# 2.net
KiCad netlist of a schematic drawn in Altium Designer
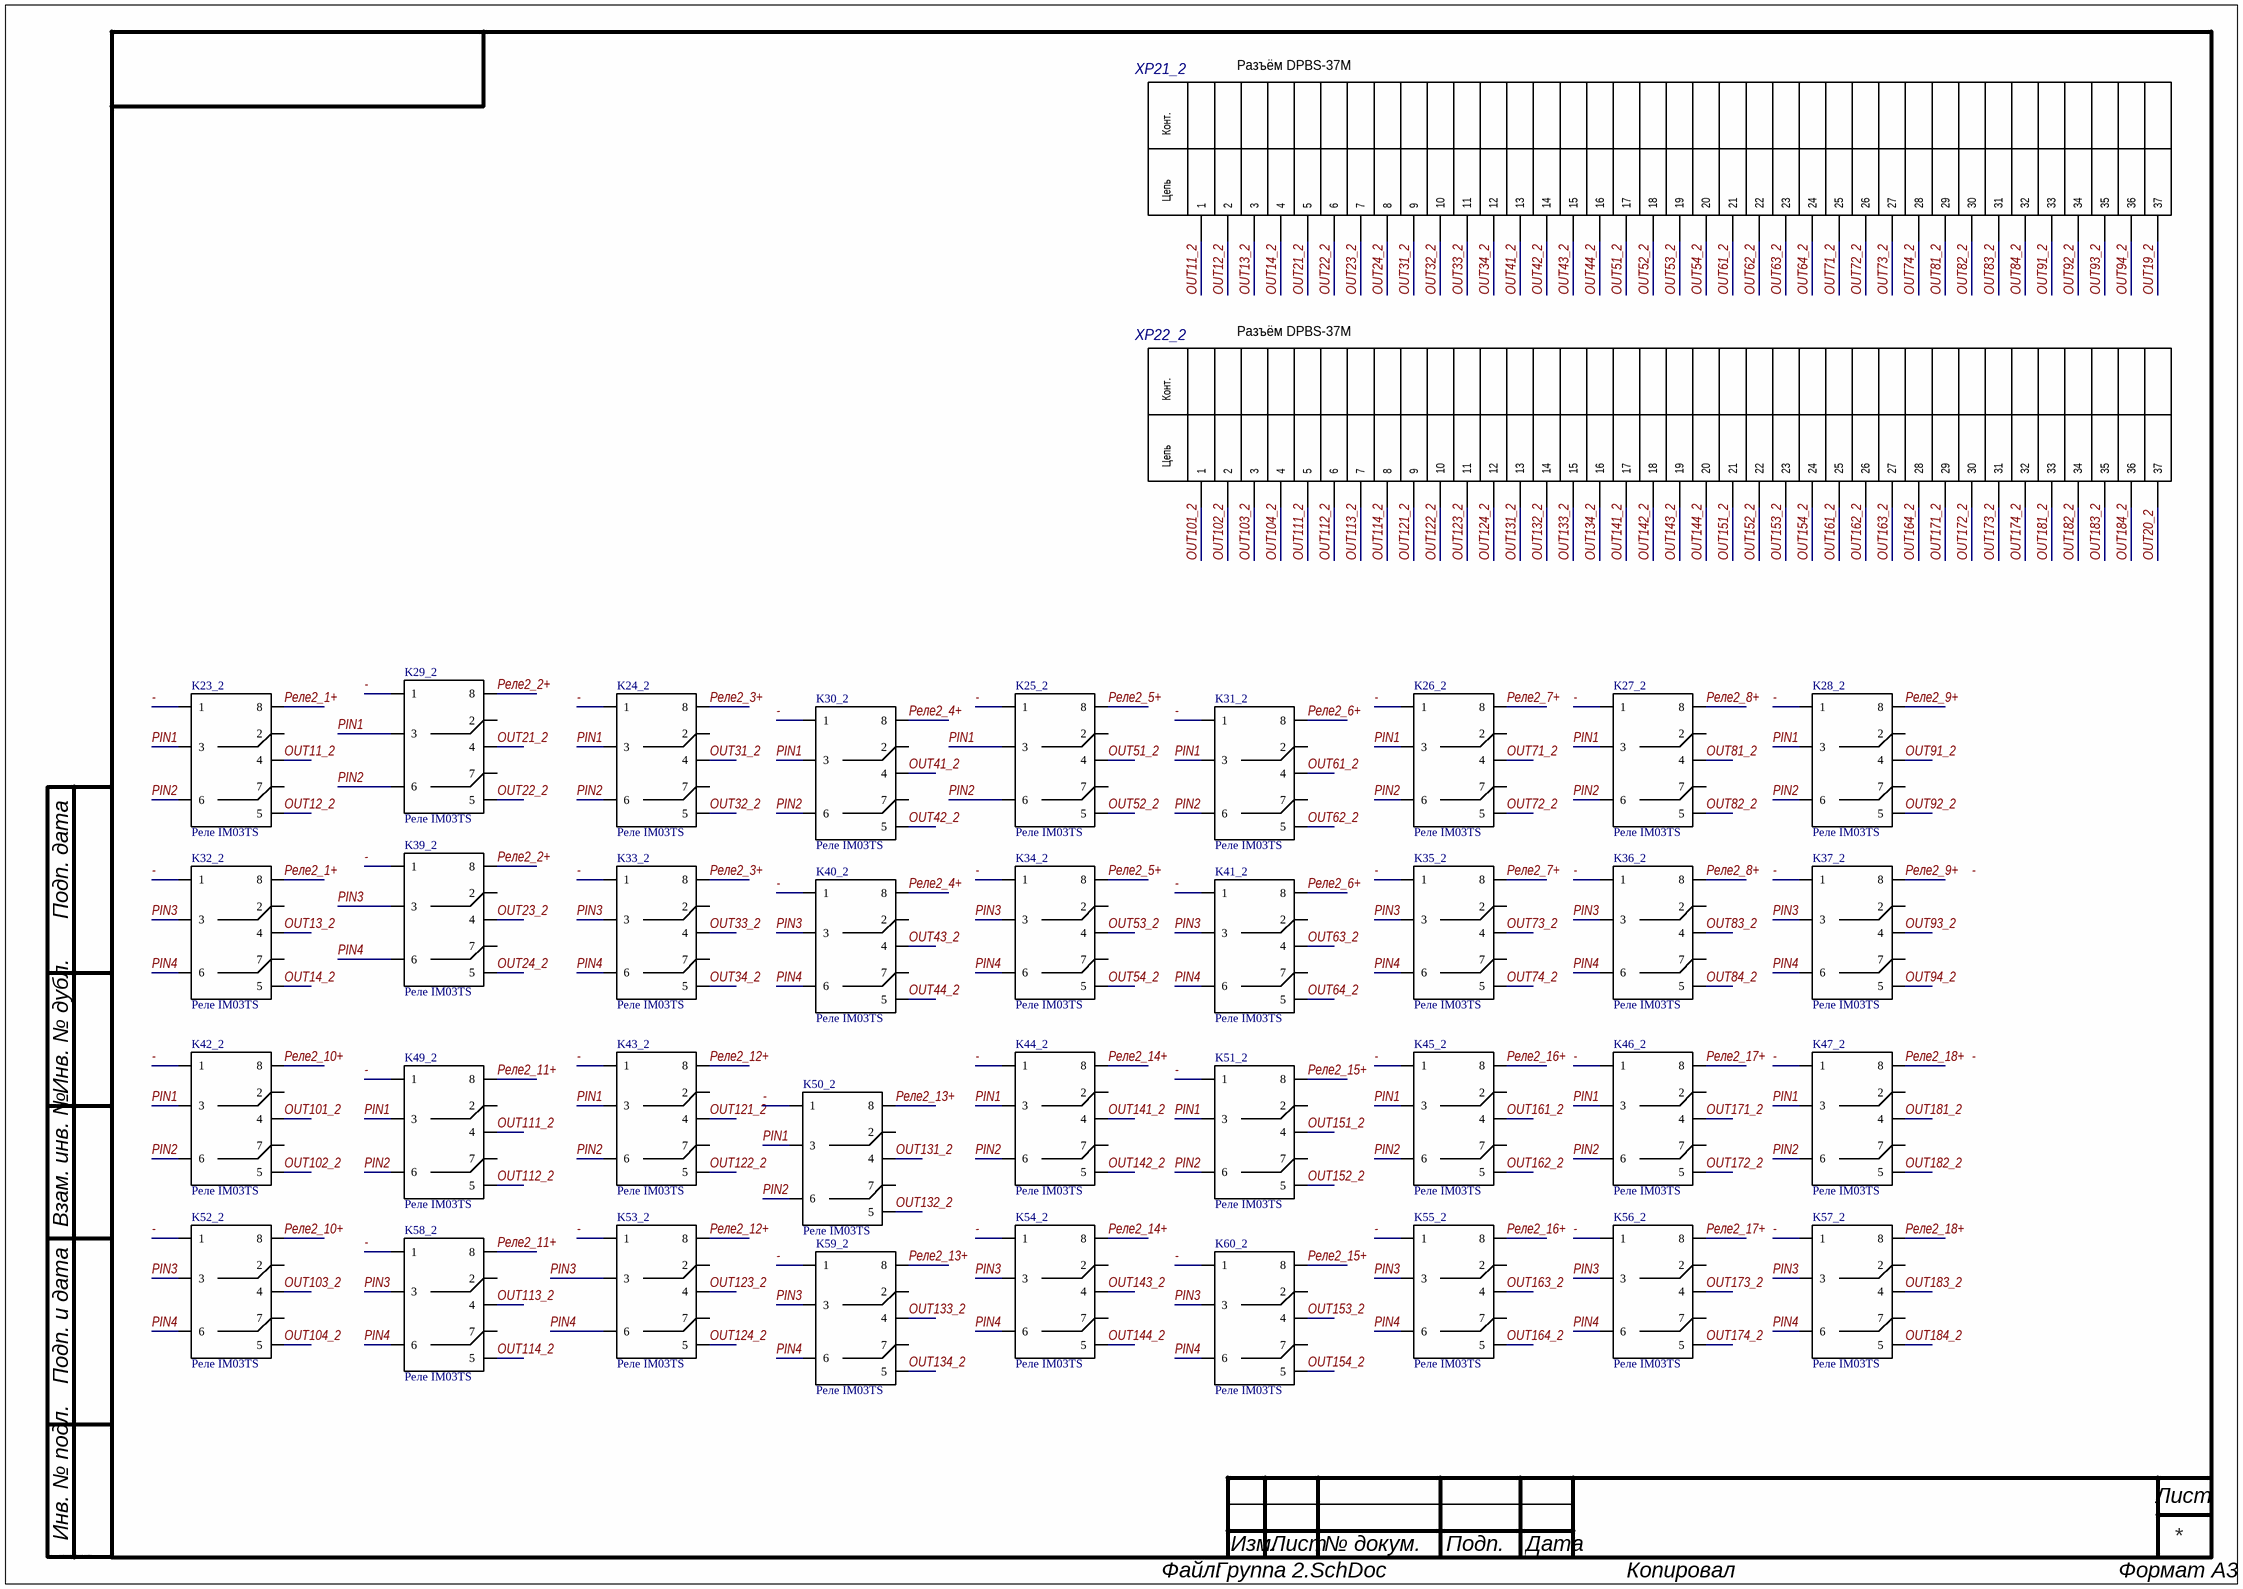
[diagram p0: Группа 2.SchDoc]

(export (version "E")
  (design (tool "Eeschema 10.0.6"))
  (components
    (comp (ref "K23_2")
      (value "Реле IM03TS")
      (footprint "IM03TS")
      (description "Реле")
      (libsource (lib "MainLibrary") (part "IM03TS"))
    )
    (comp (ref "K24_2")
      (value "Реле IM03TS")
      (footprint "IM03TS")
      (description "Реле")
      (libsource (lib "MainLibrary") (part "IM03TS"))
    )
    (comp (ref "K25_2")
      (value "Реле IM03TS")
      (footprint "IM03TS")
      (description "Реле")
      (libsource (lib "MainLibrary") (part "IM03TS"))
    )
    (comp (ref "K26_2")
      (value "Реле IM03TS")
      (footprint "IM03TS")
      (description "Реле")
      (libsource (lib "MainLibrary") (part "IM03TS"))
    )
    (comp (ref "K27_2")
      (value "Реле IM03TS")
      (footprint "IM03TS")
      (description "Реле")
      (libsource (lib "MainLibrary") (part "IM03TS"))
    )
    (comp (ref "K28_2")
      (value "Реле IM03TS")
      (footprint "IM03TS")
      (description "Реле")
      (libsource (lib "MainLibrary") (part "IM03TS"))
    )
    (comp (ref "K29_2")
      (value "Реле IM03TS")
      (footprint "IM03TS")
      (description "Реле")
      (libsource (lib "MainLibrary") (part "IM03TS"))
    )
    (comp (ref "K30_2")
      (value "Реле IM03TS")
      (footprint "IM03TS")
      (description "Реле")
      (libsource (lib "MainLibrary") (part "IM03TS"))
    )
    (comp (ref "K31_2")
      (value "Реле IM03TS")
      (footprint "IM03TS")
      (description "Реле")
      (libsource (lib "MainLibrary") (part "IM03TS"))
    )
    (comp (ref "K32_2")
      (value "Реле IM03TS")
      (footprint "IM03TS")
      (description "Реле")
      (libsource (lib "MainLibrary") (part "IM03TS"))
    )
    (comp (ref "K33_2")
      (value "Реле IM03TS")
      (footprint "IM03TS")
      (description "Реле")
      (libsource (lib "MainLibrary") (part "IM03TS"))
    )
    (comp (ref "K34_2")
      (value "Реле IM03TS")
      (footprint "IM03TS")
      (description "Реле")
      (libsource (lib "MainLibrary") (part "IM03TS"))
    )
    (comp (ref "K35_2")
      (value "Реле IM03TS")
      (footprint "IM03TS")
      (description "Реле")
      (libsource (lib "MainLibrary") (part "IM03TS"))
    )
    (comp (ref "K36_2")
      (value "Реле IM03TS")
      (footprint "IM03TS")
      (description "Реле")
      (libsource (lib "MainLibrary") (part "IM03TS"))
    )
    (comp (ref "K37_2")
      (value "Реле IM03TS")
      (footprint "IM03TS")
      (description "Реле")
      (libsource (lib "MainLibrary") (part "IM03TS"))
    )
    (comp (ref "K39_2")
      (value "Реле IM03TS")
      (footprint "IM03TS")
      (description "Реле")
      (libsource (lib "MainLibrary") (part "IM03TS"))
    )
    (comp (ref "K40_2")
      (value "Реле IM03TS")
      (footprint "IM03TS")
      (description "Реле")
      (libsource (lib "MainLibrary") (part "IM03TS"))
    )
    (comp (ref "K41_2")
      (value "Реле IM03TS")
      (footprint "IM03TS")
      (description "Реле")
      (libsource (lib "MainLibrary") (part "IM03TS"))
    )
    (comp (ref "K42_2")
      (value "Реле IM03TS")
      (footprint "IM03TS")
      (description "Реле")
      (libsource (lib "MainLibrary") (part "IM03TS"))
    )
    (comp (ref "K43_2")
      (value "Реле IM03TS")
      (footprint "IM03TS")
      (description "Реле")
      (libsource (lib "MainLibrary") (part "IM03TS"))
    )
    (comp (ref "K44_2")
      (value "Реле IM03TS")
      (footprint "IM03TS")
      (description "Реле")
      (libsource (lib "MainLibrary") (part "IM03TS"))
    )
    (comp (ref "K45_2")
      (value "Реле IM03TS")
      (footprint "IM03TS")
      (description "Реле")
      (libsource (lib "MainLibrary") (part "IM03TS"))
    )
    (comp (ref "K46_2")
      (value "Реле IM03TS")
      (footprint "IM03TS")
      (description "Реле")
      (libsource (lib "MainLibrary") (part "IM03TS"))
    )
    (comp (ref "K47_2")
      (value "Реле IM03TS")
      (footprint "IM03TS")
      (description "Реле")
      (libsource (lib "MainLibrary") (part "IM03TS"))
    )
    (comp (ref "K49_2")
      (value "Реле IM03TS")
      (footprint "IM03TS")
      (description "Реле")
      (libsource (lib "MainLibrary") (part "IM03TS"))
    )
    (comp (ref "K50_2")
      (value "Реле IM03TS")
      (footprint "IM03TS")
      (description "Реле")
      (libsource (lib "MainLibrary") (part "IM03TS"))
    )
    (comp (ref "K51_2")
      (value "Реле IM03TS")
      (footprint "IM03TS")
      (description "Реле")
      (libsource (lib "MainLibrary") (part "IM03TS"))
    )
    (comp (ref "K52_2")
      (value "Реле IM03TS")
      (footprint "IM03TS")
      (description "Реле")
      (libsource (lib "MainLibrary") (part "IM03TS"))
    )
    (comp (ref "K53_2")
      (value "Реле IM03TS")
      (footprint "IM03TS")
      (description "Реле")
      (libsource (lib "MainLibrary") (part "IM03TS"))
    )
    (comp (ref "K54_2")
      (value "Реле IM03TS")
      (footprint "IM03TS")
      (description "Реле")
      (libsource (lib "MainLibrary") (part "IM03TS"))
    )
    (comp (ref "K55_2")
      (value "Реле IM03TS")
      (footprint "IM03TS")
      (description "Реле")
      (libsource (lib "MainLibrary") (part "IM03TS"))
    )
    (comp (ref "K56_2")
      (value "Реле IM03TS")
      (footprint "IM03TS")
      (description "Реле")
      (libsource (lib "MainLibrary") (part "IM03TS"))
    )
    (comp (ref "K57_2")
      (value "Реле IM03TS")
      (footprint "IM03TS")
      (description "Реле")
      (libsource (lib "MainLibrary") (part "IM03TS"))
    )
    (comp (ref "K58_2")
      (value "Реле IM03TS")
      (footprint "IM03TS")
      (description "Реле")
      (libsource (lib "MainLibrary") (part "IM03TS"))
    )
    (comp (ref "K59_2")
      (value "Реле IM03TS")
      (footprint "IM03TS")
      (description "Реле")
      (libsource (lib "MainLibrary") (part "IM03TS"))
    )
    (comp (ref "K60_2")
      (value "Реле IM03TS")
      (footprint "IM03TS")
      (description "Реле")
      (libsource (lib "MainLibrary") (part "IM03TS"))
    )
    (comp (ref "XP21_2")
      (value "Разъём DPBS-37M")
      (footprint "DPBS-37M")
      (libsource (lib "MainLibrary") (part "DPBS-37M"))
    )
    (comp (ref "XP22_2")
      (value "Разъём DPBS-37M")
      (footprint "DPBS-37M")
      (libsource (lib "MainLibrary") (part "DPBS-37M"))
    )
  )
  (nets
    (net (code "1") (name "/-") (class "Default")
      (node (ref "K23_2") (pin "1") (pinfunction "1_1") (pintype "passive"))
      (node (ref "K24_2") (pin "1") (pinfunction "1_1") (pintype "passive"))
      (node (ref "K25_2") (pin "1") (pinfunction "1_1") (pintype "passive"))
      (node (ref "K26_2") (pin "1") (pinfunction "1_1") (pintype "passive"))
      (node (ref "K27_2") (pin "1") (pinfunction "1_1") (pintype "passive"))
      (node (ref "K28_2") (pin "1") (pinfunction "1_1") (pintype "passive"))
      (node (ref "K29_2") (pin "1") (pinfunction "1_1") (pintype "passive"))
      (node (ref "K30_2") (pin "1") (pinfunction "1_1") (pintype "passive"))
      (node (ref "K31_2") (pin "1") (pinfunction "1_1") (pintype "passive"))
      (node (ref "K32_2") (pin "1") (pinfunction "1_1") (pintype "passive"))
      (node (ref "K33_2") (pin "1") (pinfunction "1_1") (pintype "passive"))
      (node (ref "K34_2") (pin "1") (pinfunction "1_1") (pintype "passive"))
      (node (ref "K35_2") (pin "1") (pinfunction "1_1") (pintype "passive"))
      (node (ref "K36_2") (pin "1") (pinfunction "1_1") (pintype "passive"))
      (node (ref "K37_2") (pin "1") (pinfunction "1_1") (pintype "passive"))
      (node (ref "K39_2") (pin "1") (pinfunction "1_1") (pintype "passive"))
      (node (ref "K40_2") (pin "1") (pinfunction "1_1") (pintype "passive"))
      (node (ref "K41_2") (pin "1") (pinfunction "1_1") (pintype "passive"))
      (node (ref "K42_2") (pin "1") (pinfunction "1_1") (pintype "passive"))
      (node (ref "K43_2") (pin "1") (pinfunction "1_1") (pintype "passive"))
      (node (ref "K44_2") (pin "1") (pinfunction "1_1") (pintype "passive"))
      (node (ref "K45_2") (pin "1") (pinfunction "1_1") (pintype "passive"))
      (node (ref "K46_2") (pin "1") (pinfunction "1_1") (pintype "passive"))
      (node (ref "K47_2") (pin "1") (pinfunction "1_1") (pintype "passive"))
      (node (ref "K49_2") (pin "1") (pinfunction "1_1") (pintype "passive"))
      (node (ref "K50_2") (pin "1") (pinfunction "1_1") (pintype "passive"))
      (node (ref "K51_2") (pin "1") (pinfunction "1_1") (pintype "passive"))
      (node (ref "K52_2") (pin "1") (pinfunction "1_1") (pintype "passive"))
      (node (ref "K53_2") (pin "1") (pinfunction "1_1") (pintype "passive"))
      (node (ref "K54_2") (pin "1") (pinfunction "1_1") (pintype "passive"))
      (node (ref "K55_2") (pin "1") (pinfunction "1_1") (pintype "passive"))
      (node (ref "K56_2") (pin "1") (pinfunction "1_1") (pintype "passive"))
      (node (ref "K57_2") (pin "1") (pinfunction "1_1") (pintype "passive"))
      (node (ref "K58_2") (pin "1") (pinfunction "1_1") (pintype "passive"))
      (node (ref "K59_2") (pin "1") (pinfunction "1_1") (pintype "passive"))
      (node (ref "K60_2") (pin "1") (pinfunction "1_1") (pintype "passive"))
    )
    (net (code "2") (name "/OUT11_2") (class "Default")
      (node (ref "K23_2") (pin "4") (pinfunction "4_4") (pintype "passive"))
      (node (ref "XP21_2") (pin "1") (pinfunction "1_1") (pintype "passive"))
    )
    (net (code "3") (name "/OUT12_2") (class "Default")
      (node (ref "K23_2") (pin "5") (pinfunction "5_5") (pintype "passive"))
      (node (ref "XP21_2") (pin "2") (pinfunction "2_2") (pintype "passive"))
    )
    (net (code "4") (name "/OUT13_2") (class "Default")
      (node (ref "K32_2") (pin "4") (pinfunction "4_4") (pintype "passive"))
      (node (ref "XP21_2") (pin "3") (pinfunction "3_3") (pintype "passive"))
    )
    (net (code "5") (name "/OUT14_2") (class "Default")
      (node (ref "K32_2") (pin "5") (pinfunction "5_5") (pintype "passive"))
      (node (ref "XP21_2") (pin "4") (pinfunction "4_4") (pintype "passive"))
    )
    (net (code "6") (name "/OUT19_2") (class "Default")
      (node (ref "XP21_2") (pin "37") (pinfunction "37_37") (pintype "passive"))
    )
    (net (code "7") (name "/OUT20_2") (class "Default")
      (node (ref "XP22_2") (pin "37") (pinfunction "37_37") (pintype "passive"))
    )
    (net (code "8") (name "/OUT21_2") (class "Default")
      (node (ref "K29_2") (pin "4") (pinfunction "4_4") (pintype "passive"))
      (node (ref "XP21_2") (pin "5") (pinfunction "5_5") (pintype "passive"))
    )
    (net (code "9") (name "/OUT22_2") (class "Default")
      (node (ref "K29_2") (pin "5") (pinfunction "5_5") (pintype "passive"))
      (node (ref "XP21_2") (pin "6") (pinfunction "6_6") (pintype "passive"))
    )
    (net (code "10") (name "/OUT23_2") (class "Default")
      (node (ref "K39_2") (pin "4") (pinfunction "4_4") (pintype "passive"))
      (node (ref "XP21_2") (pin "7") (pinfunction "7_7") (pintype "passive"))
    )
    (net (code "11") (name "/OUT24_2") (class "Default")
      (node (ref "K39_2") (pin "5") (pinfunction "5_5") (pintype "passive"))
      (node (ref "XP21_2") (pin "8") (pinfunction "8_8") (pintype "passive"))
    )
    (net (code "12") (name "/OUT31_2") (class "Default")
      (node (ref "K24_2") (pin "4") (pinfunction "4_4") (pintype "passive"))
      (node (ref "XP21_2") (pin "9") (pinfunction "9_9") (pintype "passive"))
    )
    (net (code "13") (name "/OUT32_2") (class "Default")
      (node (ref "K24_2") (pin "5") (pinfunction "5_5") (pintype "passive"))
      (node (ref "XP21_2") (pin "10") (pinfunction "10_10") (pintype "passive"))
    )
    (net (code "14") (name "/OUT33_2") (class "Default")
      (node (ref "K33_2") (pin "4") (pinfunction "4_4") (pintype "passive"))
      (node (ref "XP21_2") (pin "11") (pinfunction "11_11") (pintype "passive"))
    )
    (net (code "15") (name "/OUT34_2") (class "Default")
      (node (ref "K33_2") (pin "5") (pinfunction "5_5") (pintype "passive"))
      (node (ref "XP21_2") (pin "12") (pinfunction "12_12") (pintype "passive"))
    )
    (net (code "16") (name "/OUT41_2") (class "Default")
      (node (ref "K30_2") (pin "4") (pinfunction "4_4") (pintype "passive"))
      (node (ref "XP21_2") (pin "13") (pinfunction "13_13") (pintype "passive"))
    )
    (net (code "17") (name "/OUT42_2") (class "Default")
      (node (ref "K30_2") (pin "5") (pinfunction "5_5") (pintype "passive"))
      (node (ref "XP21_2") (pin "14") (pinfunction "14_14") (pintype "passive"))
    )
    (net (code "18") (name "/OUT43_2") (class "Default")
      (node (ref "K40_2") (pin "4") (pinfunction "4_4") (pintype "passive"))
      (node (ref "XP21_2") (pin "15") (pinfunction "15_15") (pintype "passive"))
    )
    (net (code "19") (name "/OUT44_2") (class "Default")
      (node (ref "K40_2") (pin "5") (pinfunction "5_5") (pintype "passive"))
      (node (ref "XP21_2") (pin "16") (pinfunction "16_16") (pintype "passive"))
    )
    (net (code "20") (name "/OUT51_2") (class "Default")
      (node (ref "K25_2") (pin "4") (pinfunction "4_4") (pintype "passive"))
      (node (ref "XP21_2") (pin "17") (pinfunction "17_17") (pintype "passive"))
    )
    (net (code "21") (name "/OUT52_2") (class "Default")
      (node (ref "K25_2") (pin "5") (pinfunction "5_5") (pintype "passive"))
      (node (ref "XP21_2") (pin "18") (pinfunction "18_18") (pintype "passive"))
    )
    (net (code "22") (name "/OUT53_2") (class "Default")
      (node (ref "K34_2") (pin "4") (pinfunction "4_4") (pintype "passive"))
      (node (ref "XP21_2") (pin "19") (pinfunction "19_19") (pintype "passive"))
    )
    (net (code "23") (name "/OUT54_2") (class "Default")
      (node (ref "K34_2") (pin "5") (pinfunction "5_5") (pintype "passive"))
      (node (ref "XP21_2") (pin "20") (pinfunction "20_20") (pintype "passive"))
    )
    (net (code "24") (name "/OUT61_2") (class "Default")
      (node (ref "K31_2") (pin "4") (pinfunction "4_4") (pintype "passive"))
      (node (ref "XP21_2") (pin "21") (pinfunction "21_21") (pintype "passive"))
    )
    (net (code "25") (name "/OUT62_2") (class "Default")
      (node (ref "K31_2") (pin "5") (pinfunction "5_5") (pintype "passive"))
      (node (ref "XP21_2") (pin "22") (pinfunction "22_22") (pintype "passive"))
    )
    (net (code "26") (name "/OUT63_2") (class "Default")
      (node (ref "K41_2") (pin "4") (pinfunction "4_4") (pintype "passive"))
      (node (ref "XP21_2") (pin "23") (pinfunction "23_23") (pintype "passive"))
    )
    (net (code "27") (name "/OUT64_2") (class "Default")
      (node (ref "K41_2") (pin "5") (pinfunction "5_5") (pintype "passive"))
      (node (ref "XP21_2") (pin "24") (pinfunction "24_24") (pintype "passive"))
    )
    (net (code "28") (name "/OUT71_2") (class "Default")
      (node (ref "K26_2") (pin "4") (pinfunction "4_4") (pintype "passive"))
      (node (ref "XP21_2") (pin "25") (pinfunction "25_25") (pintype "passive"))
    )
    (net (code "29") (name "/OUT72_2") (class "Default")
      (node (ref "K26_2") (pin "5") (pinfunction "5_5") (pintype "passive"))
      (node (ref "XP21_2") (pin "26") (pinfunction "26_26") (pintype "passive"))
    )
    (net (code "30") (name "/OUT73_2") (class "Default")
      (node (ref "K35_2") (pin "4") (pinfunction "4_4") (pintype "passive"))
      (node (ref "XP21_2") (pin "27") (pinfunction "27_27") (pintype "passive"))
    )
    (net (code "31") (name "/OUT74_2") (class "Default")
      (node (ref "K35_2") (pin "5") (pinfunction "5_5") (pintype "passive"))
      (node (ref "XP21_2") (pin "28") (pinfunction "28_28") (pintype "passive"))
    )
    (net (code "32") (name "/OUT81_2") (class "Default")
      (node (ref "K27_2") (pin "4") (pinfunction "4_4") (pintype "passive"))
      (node (ref "XP21_2") (pin "29") (pinfunction "29_29") (pintype "passive"))
    )
    (net (code "33") (name "/OUT82_2") (class "Default")
      (node (ref "K27_2") (pin "5") (pinfunction "5_5") (pintype "passive"))
      (node (ref "XP21_2") (pin "30") (pinfunction "30_30") (pintype "passive"))
    )
    (net (code "34") (name "/OUT83_2") (class "Default")
      (node (ref "K36_2") (pin "4") (pinfunction "4_4") (pintype "passive"))
      (node (ref "XP21_2") (pin "31") (pinfunction "31_31") (pintype "passive"))
    )
    (net (code "35") (name "/OUT84_2") (class "Default")
      (node (ref "K36_2") (pin "5") (pinfunction "5_5") (pintype "passive"))
      (node (ref "XP21_2") (pin "32") (pinfunction "32_32") (pintype "passive"))
    )
    (net (code "36") (name "/OUT91_2") (class "Default")
      (node (ref "K28_2") (pin "4") (pinfunction "4_4") (pintype "passive"))
      (node (ref "XP21_2") (pin "33") (pinfunction "33_33") (pintype "passive"))
    )
    (net (code "37") (name "/OUT92_2") (class "Default")
      (node (ref "K28_2") (pin "5") (pinfunction "5_5") (pintype "passive"))
      (node (ref "XP21_2") (pin "34") (pinfunction "34_34") (pintype "passive"))
    )
    (net (code "38") (name "/OUT93_2") (class "Default")
      (node (ref "K37_2") (pin "4") (pinfunction "4_4") (pintype "passive"))
      (node (ref "XP21_2") (pin "35") (pinfunction "35_35") (pintype "passive"))
    )
    (net (code "39") (name "/OUT94_2") (class "Default")
      (node (ref "K37_2") (pin "5") (pinfunction "5_5") (pintype "passive"))
      (node (ref "XP21_2") (pin "36") (pinfunction "36_36") (pintype "passive"))
    )
    (net (code "40") (name "/OUT101_2") (class "Default")
      (node (ref "K42_2") (pin "4") (pinfunction "4_4") (pintype "passive"))
      (node (ref "XP22_2") (pin "1") (pinfunction "1_1") (pintype "passive"))
    )
    (net (code "41") (name "/OUT102_2") (class "Default")
      (node (ref "K42_2") (pin "5") (pinfunction "5_5") (pintype "passive"))
      (node (ref "XP22_2") (pin "2") (pinfunction "2_2") (pintype "passive"))
    )
    (net (code "42") (name "/OUT103_2") (class "Default")
      (node (ref "K52_2") (pin "4") (pinfunction "4_4") (pintype "passive"))
      (node (ref "XP22_2") (pin "3") (pinfunction "3_3") (pintype "passive"))
    )
    (net (code "43") (name "/OUT104_2") (class "Default")
      (node (ref "K52_2") (pin "5") (pinfunction "5_5") (pintype "passive"))
      (node (ref "XP22_2") (pin "4") (pinfunction "4_4") (pintype "passive"))
    )
    (net (code "44") (name "/OUT111_2") (class "Default")
      (node (ref "K49_2") (pin "4") (pinfunction "4_4") (pintype "passive"))
      (node (ref "XP22_2") (pin "5") (pinfunction "5_5") (pintype "passive"))
    )
    (net (code "45") (name "/OUT112_2") (class "Default")
      (node (ref "K49_2") (pin "5") (pinfunction "5_5") (pintype "passive"))
      (node (ref "XP22_2") (pin "6") (pinfunction "6_6") (pintype "passive"))
    )
    (net (code "46") (name "/OUT113_2") (class "Default")
      (node (ref "K58_2") (pin "4") (pinfunction "4_4") (pintype "passive"))
      (node (ref "XP22_2") (pin "7") (pinfunction "7_7") (pintype "passive"))
    )
    (net (code "47") (name "/OUT114_2") (class "Default")
      (node (ref "K58_2") (pin "5") (pinfunction "5_5") (pintype "passive"))
      (node (ref "XP22_2") (pin "8") (pinfunction "8_8") (pintype "passive"))
    )
    (net (code "48") (name "/OUT121_2") (class "Default")
      (node (ref "K43_2") (pin "4") (pinfunction "4_4") (pintype "passive"))
      (node (ref "XP22_2") (pin "9") (pinfunction "9_9") (pintype "passive"))
    )
    (net (code "49") (name "/OUT122_2") (class "Default")
      (node (ref "K43_2") (pin "5") (pinfunction "5_5") (pintype "passive"))
      (node (ref "XP22_2") (pin "10") (pinfunction "10_10") (pintype "passive"))
    )
    (net (code "50") (name "/OUT123_2") (class "Default")
      (node (ref "K53_2") (pin "4") (pinfunction "4_4") (pintype "passive"))
      (node (ref "XP22_2") (pin "11") (pinfunction "11_11") (pintype "passive"))
    )
    (net (code "51") (name "/OUT124_2") (class "Default")
      (node (ref "K53_2") (pin "5") (pinfunction "5_5") (pintype "passive"))
      (node (ref "XP22_2") (pin "12") (pinfunction "12_12") (pintype "passive"))
    )
    (net (code "52") (name "/OUT131_2") (class "Default")
      (node (ref "K50_2") (pin "4") (pinfunction "4_4") (pintype "passive"))
      (node (ref "XP22_2") (pin "13") (pinfunction "13_13") (pintype "passive"))
    )
    (net (code "53") (name "/OUT132_2") (class "Default")
      (node (ref "K50_2") (pin "5") (pinfunction "5_5") (pintype "passive"))
      (node (ref "XP22_2") (pin "14") (pinfunction "14_14") (pintype "passive"))
    )
    (net (code "54") (name "/OUT133_2") (class "Default")
      (node (ref "K59_2") (pin "4") (pinfunction "4_4") (pintype "passive"))
      (node (ref "XP22_2") (pin "15") (pinfunction "15_15") (pintype "passive"))
    )
    (net (code "55") (name "/OUT134_2") (class "Default")
      (node (ref "K59_2") (pin "5") (pinfunction "5_5") (pintype "passive"))
      (node (ref "XP22_2") (pin "16") (pinfunction "16_16") (pintype "passive"))
    )
    (net (code "56") (name "/OUT141_2") (class "Default")
      (node (ref "K44_2") (pin "4") (pinfunction "4_4") (pintype "passive"))
      (node (ref "XP22_2") (pin "17") (pinfunction "17_17") (pintype "passive"))
    )
    (net (code "57") (name "/OUT142_2") (class "Default")
      (node (ref "K44_2") (pin "5") (pinfunction "5_5") (pintype "passive"))
      (node (ref "XP22_2") (pin "18") (pinfunction "18_18") (pintype "passive"))
    )
    (net (code "58") (name "/OUT143_2") (class "Default")
      (node (ref "K54_2") (pin "4") (pinfunction "4_4") (pintype "passive"))
      (node (ref "XP22_2") (pin "19") (pinfunction "19_19") (pintype "passive"))
    )
    (net (code "59") (name "/OUT144_2") (class "Default")
      (node (ref "K54_2") (pin "5") (pinfunction "5_5") (pintype "passive"))
      (node (ref "XP22_2") (pin "20") (pinfunction "20_20") (pintype "passive"))
    )
    (net (code "60") (name "/OUT151_2") (class "Default")
      (node (ref "K51_2") (pin "4") (pinfunction "4_4") (pintype "passive"))
      (node (ref "XP22_2") (pin "21") (pinfunction "21_21") (pintype "passive"))
    )
    (net (code "61") (name "/OUT152_2") (class "Default")
      (node (ref "K51_2") (pin "5") (pinfunction "5_5") (pintype "passive"))
      (node (ref "XP22_2") (pin "22") (pinfunction "22_22") (pintype "passive"))
    )
    (net (code "62") (name "/OUT153_2") (class "Default")
      (node (ref "K60_2") (pin "4") (pinfunction "4_4") (pintype "passive"))
      (node (ref "XP22_2") (pin "23") (pinfunction "23_23") (pintype "passive"))
    )
    (net (code "63") (name "/OUT154_2") (class "Default")
      (node (ref "K60_2") (pin "5") (pinfunction "5_5") (pintype "passive"))
      (node (ref "XP22_2") (pin "24") (pinfunction "24_24") (pintype "passive"))
    )
    (net (code "64") (name "/OUT161_2") (class "Default")
      (node (ref "K45_2") (pin "4") (pinfunction "4_4") (pintype "passive"))
      (node (ref "XP22_2") (pin "25") (pinfunction "25_25") (pintype "passive"))
    )
    (net (code "65") (name "/OUT162_2") (class "Default")
      (node (ref "K45_2") (pin "5") (pinfunction "5_5") (pintype "passive"))
      (node (ref "XP22_2") (pin "26") (pinfunction "26_26") (pintype "passive"))
    )
    (net (code "66") (name "/OUT163_2") (class "Default")
      (node (ref "K55_2") (pin "4") (pinfunction "4_4") (pintype "passive"))
      (node (ref "XP22_2") (pin "27") (pinfunction "27_27") (pintype "passive"))
    )
    (net (code "67") (name "/OUT164_2") (class "Default")
      (node (ref "K55_2") (pin "5") (pinfunction "5_5") (pintype "passive"))
      (node (ref "XP22_2") (pin "28") (pinfunction "28_28") (pintype "passive"))
    )
    (net (code "68") (name "/OUT171_2") (class "Default")
      (node (ref "K46_2") (pin "4") (pinfunction "4_4") (pintype "passive"))
      (node (ref "XP22_2") (pin "29") (pinfunction "29_29") (pintype "passive"))
    )
    (net (code "69") (name "/OUT172_2") (class "Default")
      (node (ref "K46_2") (pin "5") (pinfunction "5_5") (pintype "passive"))
      (node (ref "XP22_2") (pin "30") (pinfunction "30_30") (pintype "passive"))
    )
    (net (code "70") (name "/OUT173_2") (class "Default")
      (node (ref "K56_2") (pin "4") (pinfunction "4_4") (pintype "passive"))
      (node (ref "XP22_2") (pin "31") (pinfunction "31_31") (pintype "passive"))
    )
    (net (code "71") (name "/OUT174_2") (class "Default")
      (node (ref "K56_2") (pin "5") (pinfunction "5_5") (pintype "passive"))
      (node (ref "XP22_2") (pin "32") (pinfunction "32_32") (pintype "passive"))
    )
    (net (code "72") (name "/OUT181_2") (class "Default")
      (node (ref "K47_2") (pin "4") (pinfunction "4_4") (pintype "passive"))
      (node (ref "XP22_2") (pin "33") (pinfunction "33_33") (pintype "passive"))
    )
    (net (code "73") (name "/OUT182_2") (class "Default")
      (node (ref "K47_2") (pin "5") (pinfunction "5_5") (pintype "passive"))
      (node (ref "XP22_2") (pin "34") (pinfunction "34_34") (pintype "passive"))
    )
    (net (code "74") (name "/OUT183_2") (class "Default")
      (node (ref "K57_2") (pin "4") (pinfunction "4_4") (pintype "passive"))
      (node (ref "XP22_2") (pin "35") (pinfunction "35_35") (pintype "passive"))
    )
    (net (code "75") (name "/OUT184_2") (class "Default")
      (node (ref "K57_2") (pin "5") (pinfunction "5_5") (pintype "passive"))
      (node (ref "XP22_2") (pin "36") (pinfunction "36_36") (pintype "passive"))
    )
    (net (code "76") (name "/PIN1") (class "Default")
      (node (ref "K23_2") (pin "3") (pinfunction "3_3") (pintype "passive"))
      (node (ref "K24_2") (pin "3") (pinfunction "3_3") (pintype "passive"))
      (node (ref "K25_2") (pin "3") (pinfunction "3_3") (pintype "passive"))
      (node (ref "K26_2") (pin "3") (pinfunction "3_3") (pintype "passive"))
      (node (ref "K27_2") (pin "3") (pinfunction "3_3") (pintype "passive"))
      (node (ref "K28_2") (pin "3") (pinfunction "3_3") (pintype "passive"))
      (node (ref "K29_2") (pin "3") (pinfunction "3_3") (pintype "passive"))
      (node (ref "K30_2") (pin "3") (pinfunction "3_3") (pintype "passive"))
      (node (ref "K31_2") (pin "3") (pinfunction "3_3") (pintype "passive"))
      (node (ref "K42_2") (pin "3") (pinfunction "3_3") (pintype "passive"))
      (node (ref "K43_2") (pin "3") (pinfunction "3_3") (pintype "passive"))
      (node (ref "K44_2") (pin "3") (pinfunction "3_3") (pintype "passive"))
      (node (ref "K45_2") (pin "3") (pinfunction "3_3") (pintype "passive"))
      (node (ref "K46_2") (pin "3") (pinfunction "3_3") (pintype "passive"))
      (node (ref "K47_2") (pin "3") (pinfunction "3_3") (pintype "passive"))
      (node (ref "K49_2") (pin "3") (pinfunction "3_3") (pintype "passive"))
      (node (ref "K50_2") (pin "3") (pinfunction "3_3") (pintype "passive"))
      (node (ref "K51_2") (pin "3") (pinfunction "3_3") (pintype "passive"))
    )
    (net (code "77") (name "/PIN2") (class "Default")
      (node (ref "K23_2") (pin "6") (pinfunction "6_6") (pintype "passive"))
      (node (ref "K24_2") (pin "6") (pinfunction "6_6") (pintype "passive"))
      (node (ref "K25_2") (pin "6") (pinfunction "6_6") (pintype "passive"))
      (node (ref "K26_2") (pin "6") (pinfunction "6_6") (pintype "passive"))
      (node (ref "K27_2") (pin "6") (pinfunction "6_6") (pintype "passive"))
      (node (ref "K28_2") (pin "6") (pinfunction "6_6") (pintype "passive"))
      (node (ref "K29_2") (pin "6") (pinfunction "6_6") (pintype "passive"))
      (node (ref "K30_2") (pin "6") (pinfunction "6_6") (pintype "passive"))
      (node (ref "K31_2") (pin "6") (pinfunction "6_6") (pintype "passive"))
      (node (ref "K42_2") (pin "6") (pinfunction "6_6") (pintype "passive"))
      (node (ref "K43_2") (pin "6") (pinfunction "6_6") (pintype "passive"))
      (node (ref "K44_2") (pin "6") (pinfunction "6_6") (pintype "passive"))
      (node (ref "K45_2") (pin "6") (pinfunction "6_6") (pintype "passive"))
      (node (ref "K46_2") (pin "6") (pinfunction "6_6") (pintype "passive"))
      (node (ref "K47_2") (pin "6") (pinfunction "6_6") (pintype "passive"))
      (node (ref "K49_2") (pin "6") (pinfunction "6_6") (pintype "passive"))
      (node (ref "K50_2") (pin "6") (pinfunction "6_6") (pintype "passive"))
      (node (ref "K51_2") (pin "6") (pinfunction "6_6") (pintype "passive"))
    )
    (net (code "78") (name "/PIN3") (class "Default")
      (node (ref "K32_2") (pin "3") (pinfunction "3_3") (pintype "passive"))
      (node (ref "K33_2") (pin "3") (pinfunction "3_3") (pintype "passive"))
      (node (ref "K34_2") (pin "3") (pinfunction "3_3") (pintype "passive"))
      (node (ref "K35_2") (pin "3") (pinfunction "3_3") (pintype "passive"))
      (node (ref "K36_2") (pin "3") (pinfunction "3_3") (pintype "passive"))
      (node (ref "K37_2") (pin "3") (pinfunction "3_3") (pintype "passive"))
      (node (ref "K39_2") (pin "3") (pinfunction "3_3") (pintype "passive"))
      (node (ref "K40_2") (pin "3") (pinfunction "3_3") (pintype "passive"))
      (node (ref "K41_2") (pin "3") (pinfunction "3_3") (pintype "passive"))
      (node (ref "K52_2") (pin "3") (pinfunction "3_3") (pintype "passive"))
      (node (ref "K53_2") (pin "3") (pinfunction "3_3") (pintype "passive"))
      (node (ref "K54_2") (pin "3") (pinfunction "3_3") (pintype "passive"))
      (node (ref "K55_2") (pin "3") (pinfunction "3_3") (pintype "passive"))
      (node (ref "K56_2") (pin "3") (pinfunction "3_3") (pintype "passive"))
      (node (ref "K57_2") (pin "3") (pinfunction "3_3") (pintype "passive"))
      (node (ref "K58_2") (pin "3") (pinfunction "3_3") (pintype "passive"))
      (node (ref "K59_2") (pin "3") (pinfunction "3_3") (pintype "passive"))
      (node (ref "K60_2") (pin "3") (pinfunction "3_3") (pintype "passive"))
    )
    (net (code "79") (name "/PIN4") (class "Default")
      (node (ref "K32_2") (pin "6") (pinfunction "6_6") (pintype "passive"))
      (node (ref "K33_2") (pin "6") (pinfunction "6_6") (pintype "passive"))
      (node (ref "K34_2") (pin "6") (pinfunction "6_6") (pintype "passive"))
      (node (ref "K35_2") (pin "6") (pinfunction "6_6") (pintype "passive"))
      (node (ref "K36_2") (pin "6") (pinfunction "6_6") (pintype "passive"))
      (node (ref "K37_2") (pin "6") (pinfunction "6_6") (pintype "passive"))
      (node (ref "K39_2") (pin "6") (pinfunction "6_6") (pintype "passive"))
      (node (ref "K40_2") (pin "6") (pinfunction "6_6") (pintype "passive"))
      (node (ref "K41_2") (pin "6") (pinfunction "6_6") (pintype "passive"))
      (node (ref "K52_2") (pin "6") (pinfunction "6_6") (pintype "passive"))
      (node (ref "K53_2") (pin "6") (pinfunction "6_6") (pintype "passive"))
      (node (ref "K54_2") (pin "6") (pinfunction "6_6") (pintype "passive"))
      (node (ref "K55_2") (pin "6") (pinfunction "6_6") (pintype "passive"))
      (node (ref "K56_2") (pin "6") (pinfunction "6_6") (pintype "passive"))
      (node (ref "K57_2") (pin "6") (pinfunction "6_6") (pintype "passive"))
      (node (ref "K58_2") (pin "6") (pinfunction "6_6") (pintype "passive"))
      (node (ref "K59_2") (pin "6") (pinfunction "6_6") (pintype "passive"))
      (node (ref "K60_2") (pin "6") (pinfunction "6_6") (pintype "passive"))
    )
    (net (code "80") (name "/Реле2_1+") (class "Default")
      (node (ref "K23_2") (pin "8") (pinfunction "8_8") (pintype "passive"))
      (node (ref "K32_2") (pin "8") (pinfunction "8_8") (pintype "passive"))
    )
    (net (code "81") (name "/Реле2_2+") (class "Default")
      (node (ref "K29_2") (pin "8") (pinfunction "8_8") (pintype "passive"))
      (node (ref "K39_2") (pin "8") (pinfunction "8_8") (pintype "passive"))
    )
    (net (code "82") (name "/Реле2_3+") (class "Default")
      (node (ref "K24_2") (pin "8") (pinfunction "8_8") (pintype "passive"))
      (node (ref "K33_2") (pin "8") (pinfunction "8_8") (pintype "passive"))
    )
    (net (code "83") (name "/Реле2_4+") (class "Default")
      (node (ref "K30_2") (pin "8") (pinfunction "8_8") (pintype "passive"))
      (node (ref "K40_2") (pin "8") (pinfunction "8_8") (pintype "passive"))
    )
    (net (code "84") (name "/Реле2_5+") (class "Default")
      (node (ref "K25_2") (pin "8") (pinfunction "8_8") (pintype "passive"))
      (node (ref "K34_2") (pin "8") (pinfunction "8_8") (pintype "passive"))
    )
    (net (code "85") (name "/Реле2_6+") (class "Default")
      (node (ref "K31_2") (pin "8") (pinfunction "8_8") (pintype "passive"))
      (node (ref "K41_2") (pin "8") (pinfunction "8_8") (pintype "passive"))
    )
    (net (code "86") (name "/Реле2_7+") (class "Default")
      (node (ref "K26_2") (pin "8") (pinfunction "8_8") (pintype "passive"))
      (node (ref "K35_2") (pin "8") (pinfunction "8_8") (pintype "passive"))
    )
    (net (code "87") (name "/Реле2_8+") (class "Default")
      (node (ref "K27_2") (pin "8") (pinfunction "8_8") (pintype "passive"))
      (node (ref "K36_2") (pin "8") (pinfunction "8_8") (pintype "passive"))
    )
    (net (code "88") (name "/Реле2_9+") (class "Default")
      (node (ref "K28_2") (pin "8") (pinfunction "8_8") (pintype "passive"))
      (node (ref "K37_2") (pin "8") (pinfunction "8_8") (pintype "passive"))
    )
    (net (code "89") (name "/Реле2_10+") (class "Default")
      (node (ref "K42_2") (pin "8") (pinfunction "8_8") (pintype "passive"))
      (node (ref "K52_2") (pin "8") (pinfunction "8_8") (pintype "passive"))
    )
    (net (code "90") (name "/Реле2_11+") (class "Default")
      (node (ref "K49_2") (pin "8") (pinfunction "8_8") (pintype "passive"))
      (node (ref "K58_2") (pin "8") (pinfunction "8_8") (pintype "passive"))
    )
    (net (code "91") (name "/Реле2_12+") (class "Default")
      (node (ref "K43_2") (pin "8") (pinfunction "8_8") (pintype "passive"))
      (node (ref "K53_2") (pin "8") (pinfunction "8_8") (pintype "passive"))
    )
    (net (code "92") (name "/Реле2_13+") (class "Default")
      (node (ref "K50_2") (pin "8") (pinfunction "8_8") (pintype "passive"))
      (node (ref "K59_2") (pin "8") (pinfunction "8_8") (pintype "passive"))
    )
    (net (code "93") (name "/Реле2_14+") (class "Default")
      (node (ref "K44_2") (pin "8") (pinfunction "8_8") (pintype "passive"))
      (node (ref "K54_2") (pin "8") (pinfunction "8_8") (pintype "passive"))
    )
    (net (code "94") (name "/Реле2_15+") (class "Default")
      (node (ref "K51_2") (pin "8") (pinfunction "8_8") (pintype "passive"))
      (node (ref "K60_2") (pin "8") (pinfunction "8_8") (pintype "passive"))
    )
    (net (code "95") (name "/Реле2_16+") (class "Default")
      (node (ref "K45_2") (pin "8") (pinfunction "8_8") (pintype "passive"))
      (node (ref "K55_2") (pin "8") (pinfunction "8_8") (pintype "passive"))
    )
    (net (code "96") (name "/Реле2_17+") (class "Default")
      (node (ref "K46_2") (pin "8") (pinfunction "8_8") (pintype "passive"))
      (node (ref "K56_2") (pin "8") (pinfunction "8_8") (pintype "passive"))
    )
    (net (code "97") (name "/Реле2_18+") (class "Default")
      (node (ref "K47_2") (pin "8") (pinfunction "8_8") (pintype "passive"))
      (node (ref "K57_2") (pin "8") (pinfunction "8_8") (pintype "passive"))
    )
    (net (code "98") (name "unconnected-(K23_2-Pad2)") (class "Default")
      (node (ref "K23_2") (pin "2") (pinfunction "2_2") (pintype "passive"))
    )
    (net (code "99") (name "unconnected-(K23_2-Pad7)") (class "Default")
      (node (ref "K23_2") (pin "7") (pinfunction "7_7") (pintype "passive"))
    )
    (net (code "100") (name "unconnected-(K24_2-Pad2)") (class "Default")
      (node (ref "K24_2") (pin "2") (pinfunction "2_2") (pintype "passive"))
    )
    (net (code "101") (name "unconnected-(K24_2-Pad7)") (class "Default")
      (node (ref "K24_2") (pin "7") (pinfunction "7_7") (pintype "passive"))
    )
    (net (code "102") (name "unconnected-(K25_2-Pad2)") (class "Default")
      (node (ref "K25_2") (pin "2") (pinfunction "2_2") (pintype "passive"))
    )
    (net (code "103") (name "unconnected-(K25_2-Pad7)") (class "Default")
      (node (ref "K25_2") (pin "7") (pinfunction "7_7") (pintype "passive"))
    )
    (net (code "104") (name "unconnected-(K26_2-Pad2)") (class "Default")
      (node (ref "K26_2") (pin "2") (pinfunction "2_2") (pintype "passive"))
    )
    (net (code "105") (name "unconnected-(K26_2-Pad7)") (class "Default")
      (node (ref "K26_2") (pin "7") (pinfunction "7_7") (pintype "passive"))
    )
    (net (code "106") (name "unconnected-(K27_2-Pad2)") (class "Default")
      (node (ref "K27_2") (pin "2") (pinfunction "2_2") (pintype "passive"))
    )
    (net (code "107") (name "unconnected-(K27_2-Pad7)") (class "Default")
      (node (ref "K27_2") (pin "7") (pinfunction "7_7") (pintype "passive"))
    )
    (net (code "108") (name "unconnected-(K28_2-Pad2)") (class "Default")
      (node (ref "K28_2") (pin "2") (pinfunction "2_2") (pintype "passive"))
    )
    (net (code "109") (name "unconnected-(K28_2-Pad7)") (class "Default")
      (node (ref "K28_2") (pin "7") (pinfunction "7_7") (pintype "passive"))
    )
    (net (code "110") (name "unconnected-(K29_2-Pad2)") (class "Default")
      (node (ref "K29_2") (pin "2") (pinfunction "2_2") (pintype "passive"))
    )
    (net (code "111") (name "unconnected-(K29_2-Pad7)") (class "Default")
      (node (ref "K29_2") (pin "7") (pinfunction "7_7") (pintype "passive"))
    )
    (net (code "112") (name "unconnected-(K30_2-Pad2)") (class "Default")
      (node (ref "K30_2") (pin "2") (pinfunction "2_2") (pintype "passive"))
    )
    (net (code "113") (name "unconnected-(K30_2-Pad7)") (class "Default")
      (node (ref "K30_2") (pin "7") (pinfunction "7_7") (pintype "passive"))
    )
    (net (code "114") (name "unconnected-(K31_2-Pad2)") (class "Default")
      (node (ref "K31_2") (pin "2") (pinfunction "2_2") (pintype "passive"))
    )
    (net (code "115") (name "unconnected-(K31_2-Pad7)") (class "Default")
      (node (ref "K31_2") (pin "7") (pinfunction "7_7") (pintype "passive"))
    )
    (net (code "116") (name "unconnected-(K32_2-Pad2)") (class "Default")
      (node (ref "K32_2") (pin "2") (pinfunction "2_2") (pintype "passive"))
    )
    (net (code "117") (name "unconnected-(K32_2-Pad7)") (class "Default")
      (node (ref "K32_2") (pin "7") (pinfunction "7_7") (pintype "passive"))
    )
    (net (code "118") (name "unconnected-(K33_2-Pad2)") (class "Default")
      (node (ref "K33_2") (pin "2") (pinfunction "2_2") (pintype "passive"))
    )
    (net (code "119") (name "unconnected-(K33_2-Pad7)") (class "Default")
      (node (ref "K33_2") (pin "7") (pinfunction "7_7") (pintype "passive"))
    )
    (net (code "120") (name "unconnected-(K34_2-Pad2)") (class "Default")
      (node (ref "K34_2") (pin "2") (pinfunction "2_2") (pintype "passive"))
    )
    (net (code "121") (name "unconnected-(K34_2-Pad7)") (class "Default")
      (node (ref "K34_2") (pin "7") (pinfunction "7_7") (pintype "passive"))
    )
    (net (code "122") (name "unconnected-(K35_2-Pad2)") (class "Default")
      (node (ref "K35_2") (pin "2") (pinfunction "2_2") (pintype "passive"))
    )
    (net (code "123") (name "unconnected-(K35_2-Pad7)") (class "Default")
      (node (ref "K35_2") (pin "7") (pinfunction "7_7") (pintype "passive"))
    )
    (net (code "124") (name "unconnected-(K36_2-Pad2)") (class "Default")
      (node (ref "K36_2") (pin "2") (pinfunction "2_2") (pintype "passive"))
    )
    (net (code "125") (name "unconnected-(K36_2-Pad7)") (class "Default")
      (node (ref "K36_2") (pin "7") (pinfunction "7_7") (pintype "passive"))
    )
    (net (code "126") (name "unconnected-(K37_2-Pad2)") (class "Default")
      (node (ref "K37_2") (pin "2") (pinfunction "2_2") (pintype "passive"))
    )
    (net (code "127") (name "unconnected-(K37_2-Pad7)") (class "Default")
      (node (ref "K37_2") (pin "7") (pinfunction "7_7") (pintype "passive"))
    )
    (net (code "128") (name "unconnected-(K39_2-Pad2)") (class "Default")
      (node (ref "K39_2") (pin "2") (pinfunction "2_2") (pintype "passive"))
    )
    (net (code "129") (name "unconnected-(K39_2-Pad7)") (class "Default")
      (node (ref "K39_2") (pin "7") (pinfunction "7_7") (pintype "passive"))
    )
    (net (code "130") (name "unconnected-(K40_2-Pad2)") (class "Default")
      (node (ref "K40_2") (pin "2") (pinfunction "2_2") (pintype "passive"))
    )
    (net (code "131") (name "unconnected-(K40_2-Pad7)") (class "Default")
      (node (ref "K40_2") (pin "7") (pinfunction "7_7") (pintype "passive"))
    )
    (net (code "132") (name "unconnected-(K41_2-Pad2)") (class "Default")
      (node (ref "K41_2") (pin "2") (pinfunction "2_2") (pintype "passive"))
    )
    (net (code "133") (name "unconnected-(K41_2-Pad7)") (class "Default")
      (node (ref "K41_2") (pin "7") (pinfunction "7_7") (pintype "passive"))
    )
    (net (code "134") (name "unconnected-(K42_2-Pad2)") (class "Default")
      (node (ref "K42_2") (pin "2") (pinfunction "2_2") (pintype "passive"))
    )
    (net (code "135") (name "unconnected-(K42_2-Pad7)") (class "Default")
      (node (ref "K42_2") (pin "7") (pinfunction "7_7") (pintype "passive"))
    )
    (net (code "136") (name "unconnected-(K43_2-Pad2)") (class "Default")
      (node (ref "K43_2") (pin "2") (pinfunction "2_2") (pintype "passive"))
    )
    (net (code "137") (name "unconnected-(K43_2-Pad7)") (class "Default")
      (node (ref "K43_2") (pin "7") (pinfunction "7_7") (pintype "passive"))
    )
    (net (code "138") (name "unconnected-(K44_2-Pad2)") (class "Default")
      (node (ref "K44_2") (pin "2") (pinfunction "2_2") (pintype "passive"))
    )
    (net (code "139") (name "unconnected-(K44_2-Pad7)") (class "Default")
      (node (ref "K44_2") (pin "7") (pinfunction "7_7") (pintype "passive"))
    )
    (net (code "140") (name "unconnected-(K45_2-Pad2)") (class "Default")
      (node (ref "K45_2") (pin "2") (pinfunction "2_2") (pintype "passive"))
    )
    (net (code "141") (name "unconnected-(K45_2-Pad7)") (class "Default")
      (node (ref "K45_2") (pin "7") (pinfunction "7_7") (pintype "passive"))
    )
    (net (code "142") (name "unconnected-(K46_2-Pad2)") (class "Default")
      (node (ref "K46_2") (pin "2") (pinfunction "2_2") (pintype "passive"))
    )
    (net (code "143") (name "unconnected-(K46_2-Pad7)") (class "Default")
      (node (ref "K46_2") (pin "7") (pinfunction "7_7") (pintype "passive"))
    )
    (net (code "144") (name "unconnected-(K47_2-Pad2)") (class "Default")
      (node (ref "K47_2") (pin "2") (pinfunction "2_2") (pintype "passive"))
    )
    (net (code "145") (name "unconnected-(K47_2-Pad7)") (class "Default")
      (node (ref "K47_2") (pin "7") (pinfunction "7_7") (pintype "passive"))
    )
    (net (code "146") (name "unconnected-(K49_2-Pad2)") (class "Default")
      (node (ref "K49_2") (pin "2") (pinfunction "2_2") (pintype "passive"))
    )
    (net (code "147") (name "unconnected-(K49_2-Pad7)") (class "Default")
      (node (ref "K49_2") (pin "7") (pinfunction "7_7") (pintype "passive"))
    )
    (net (code "148") (name "unconnected-(K50_2-Pad2)") (class "Default")
      (node (ref "K50_2") (pin "2") (pinfunction "2_2") (pintype "passive"))
    )
    (net (code "149") (name "unconnected-(K50_2-Pad7)") (class "Default")
      (node (ref "K50_2") (pin "7") (pinfunction "7_7") (pintype "passive"))
    )
    (net (code "150") (name "unconnected-(K51_2-Pad2)") (class "Default")
      (node (ref "K51_2") (pin "2") (pinfunction "2_2") (pintype "passive"))
    )
    (net (code "151") (name "unconnected-(K51_2-Pad7)") (class "Default")
      (node (ref "K51_2") (pin "7") (pinfunction "7_7") (pintype "passive"))
    )
    (net (code "152") (name "unconnected-(K52_2-Pad2)") (class "Default")
      (node (ref "K52_2") (pin "2") (pinfunction "2_2") (pintype "passive"))
    )
    (net (code "153") (name "unconnected-(K52_2-Pad7)") (class "Default")
      (node (ref "K52_2") (pin "7") (pinfunction "7_7") (pintype "passive"))
    )
    (net (code "154") (name "unconnected-(K53_2-Pad2)") (class "Default")
      (node (ref "K53_2") (pin "2") (pinfunction "2_2") (pintype "passive"))
    )
    (net (code "155") (name "unconnected-(K53_2-Pad7)") (class "Default")
      (node (ref "K53_2") (pin "7") (pinfunction "7_7") (pintype "passive"))
    )
    (net (code "156") (name "unconnected-(K54_2-Pad2)") (class "Default")
      (node (ref "K54_2") (pin "2") (pinfunction "2_2") (pintype "passive"))
    )
    (net (code "157") (name "unconnected-(K54_2-Pad7)") (class "Default")
      (node (ref "K54_2") (pin "7") (pinfunction "7_7") (pintype "passive"))
    )
    (net (code "158") (name "unconnected-(K55_2-Pad2)") (class "Default")
      (node (ref "K55_2") (pin "2") (pinfunction "2_2") (pintype "passive"))
    )
    (net (code "159") (name "unconnected-(K55_2-Pad7)") (class "Default")
      (node (ref "K55_2") (pin "7") (pinfunction "7_7") (pintype "passive"))
    )
    (net (code "160") (name "unconnected-(K56_2-Pad2)") (class "Default")
      (node (ref "K56_2") (pin "2") (pinfunction "2_2") (pintype "passive"))
    )
    (net (code "161") (name "unconnected-(K56_2-Pad7)") (class "Default")
      (node (ref "K56_2") (pin "7") (pinfunction "7_7") (pintype "passive"))
    )
    (net (code "162") (name "unconnected-(K57_2-Pad2)") (class "Default")
      (node (ref "K57_2") (pin "2") (pinfunction "2_2") (pintype "passive"))
    )
    (net (code "163") (name "unconnected-(K57_2-Pad7)") (class "Default")
      (node (ref "K57_2") (pin "7") (pinfunction "7_7") (pintype "passive"))
    )
    (net (code "164") (name "unconnected-(K58_2-Pad2)") (class "Default")
      (node (ref "K58_2") (pin "2") (pinfunction "2_2") (pintype "passive"))
    )
    (net (code "165") (name "unconnected-(K58_2-Pad7)") (class "Default")
      (node (ref "K58_2") (pin "7") (pinfunction "7_7") (pintype "passive"))
    )
    (net (code "166") (name "unconnected-(K59_2-Pad2)") (class "Default")
      (node (ref "K59_2") (pin "2") (pinfunction "2_2") (pintype "passive"))
    )
    (net (code "167") (name "unconnected-(K59_2-Pad7)") (class "Default")
      (node (ref "K59_2") (pin "7") (pinfunction "7_7") (pintype "passive"))
    )
    (net (code "168") (name "unconnected-(K60_2-Pad2)") (class "Default")
      (node (ref "K60_2") (pin "2") (pinfunction "2_2") (pintype "passive"))
    )
    (net (code "169") (name "unconnected-(K60_2-Pad7)") (class "Default")
      (node (ref "K60_2") (pin "7") (pinfunction "7_7") (pintype "passive"))
    )
  )
)
